# Final.net
KiCad netlist of a schematic drawn in EAGLE
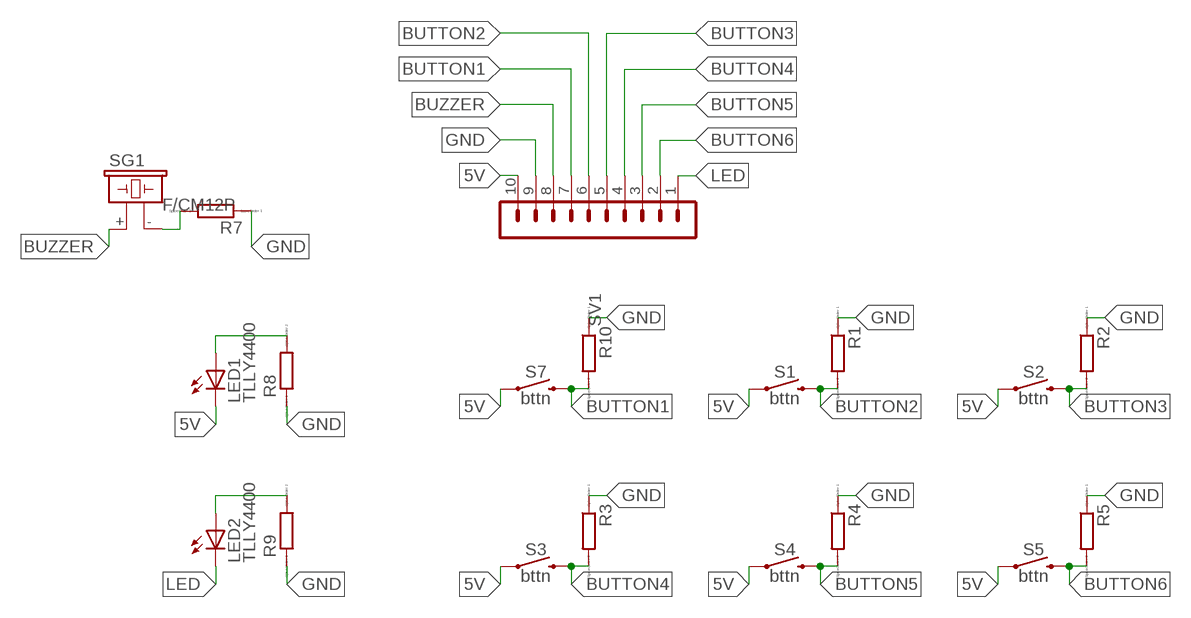
[diagram p0: schematic, sheet 1]

(export (version "E")
  (design (tool "Eeschema 10.0.6"))
  (components
    (comp (ref "LED1")
      (value "TLLY4400")
      (footprint "eagle-import:LED3MM")
      (fields (field (name "MF") "VISHAY SEMICONDUCTOR"))
      (libsource (lib "eagle-import") (part "TLLY4400"))
    )
    (comp (ref "LED2")
      (value "TLLY4400")
      (footprint "eagle-import:LED3MM")
      (fields (field (name "MF") "VISHAY SEMICONDUCTOR"))
      (libsource (lib "eagle-import") (part "TLLY4400"))
    )
    (comp (ref "R1")
      (value "R0204/7")
      (footprint "eagle-import:0204_7")
      (libsource (lib "eagle-import") (part "R0204/7"))
    )
    (comp (ref "R2")
      (value "R0204/7")
      (footprint "eagle-import:0204_7")
      (libsource (lib "eagle-import") (part "R0204/7"))
    )
    (comp (ref "R3")
      (value "R0204/7")
      (footprint "eagle-import:0204_7")
      (libsource (lib "eagle-import") (part "R0204/7"))
    )
    (comp (ref "R4")
      (value "R0204/7")
      (footprint "eagle-import:0204_7")
      (libsource (lib "eagle-import") (part "R0204/7"))
    )
    (comp (ref "R5")
      (value "R0204/7")
      (footprint "eagle-import:0204_7")
      (libsource (lib "eagle-import") (part "R0204/7"))
    )
    (comp (ref "R7")
      (value "R0204/7")
      (footprint "eagle-import:0204_7")
      (libsource (lib "eagle-import") (part "R0204/7"))
    )
    (comp (ref "R8")
      (value "R0204/7")
      (footprint "eagle-import:0204_7")
      (libsource (lib "eagle-import") (part "R0204/7"))
    )
    (comp (ref "R9")
      (value "R0204/7")
      (footprint "eagle-import:0204_7")
      (libsource (lib "eagle-import") (part "R0204/7"))
    )
    (comp (ref "R10")
      (value "R0204/7")
      (footprint "eagle-import:0204_7")
      (libsource (lib "eagle-import") (part "R0204/7"))
    )
    (comp (ref "S1")
      (value "bttn")
      (footprint "eagle-import:TACTILE_SWITCH_PTH_6.0MM")
      (libsource (lib "eagle-import") (part "MOMENTARY-SWITCH-SPST-PTH-6.0MM"))
    )
    (comp (ref "S2")
      (value "bttn")
      (footprint "eagle-import:TACTILE_SWITCH_PTH_6.0MM")
      (libsource (lib "eagle-import") (part "MOMENTARY-SWITCH-SPST-PTH-6.0MM"))
    )
    (comp (ref "S3")
      (value "bttn")
      (footprint "eagle-import:TACTILE_SWITCH_PTH_6.0MM")
      (libsource (lib "eagle-import") (part "MOMENTARY-SWITCH-SPST-PTH-6.0MM"))
    )
    (comp (ref "S4")
      (value "bttn")
      (footprint "eagle-import:TACTILE_SWITCH_PTH_6.0MM")
      (libsource (lib "eagle-import") (part "MOMENTARY-SWITCH-SPST-PTH-6.0MM"))
    )
    (comp (ref "S5")
      (value "bttn")
      (footprint "eagle-import:TACTILE_SWITCH_PTH_6.0MM")
      (libsource (lib "eagle-import") (part "MOMENTARY-SWITCH-SPST-PTH-6.0MM"))
    )
    (comp (ref "S7")
      (value "bttn")
      (footprint "eagle-import:TACTILE_SWITCH_PTH_6.0MM")
      (libsource (lib "eagle-import") (part "MOMENTARY-SWITCH-SPST-PTH-6.0MM"))
    )
    (comp (ref "SG1")
      (value "F/CM12P")
      (footprint "eagle-import:F_CM12P")
      (libsource (lib "eagle-import") (part "F/CM12P"))
    )
    (comp (ref "SV1")
      (value "MA10-1")
      (footprint "eagle-import:MA10-1")
      (libsource (lib "eagle-import") (part "MA10-1"))
    )
  )
  (nets
    (net (code "1") (name "5V") (class "Default")
      (node (ref "LED1") (pin "K") (pinfunction "C_K") (pintype "passive"))
      (node (ref "S1") (pin "1") (pinfunction "1_1") (pintype "passive"))
      (node (ref "S2") (pin "1") (pinfunction "1_1") (pintype "passive"))
      (node (ref "S3") (pin "1") (pinfunction "1_1") (pintype "passive"))
      (node (ref "S4") (pin "1") (pinfunction "1_1") (pintype "passive"))
      (node (ref "S5") (pin "1") (pinfunction "1_1") (pintype "passive"))
      (node (ref "S7") (pin "1") (pinfunction "1_1") (pintype "passive"))
      (node (ref "SV1") (pin "10") (pinfunction "10_10") (pintype "passive"))
    )
    (net (code "2") (name "BUTTON1") (class "Default")
      (node (ref "R10") (pin "2") (pinfunction "2_2") (pintype "passive"))
      (node (ref "S7") (pin "3") (pinfunction "2_3") (pintype "passive"))
      (node (ref "SV1") (pin "7") (pinfunction "7_7") (pintype "passive"))
    )
    (net (code "3") (name "BUTTON2") (class "Default")
      (node (ref "R1") (pin "2") (pinfunction "2_2") (pintype "passive"))
      (node (ref "S1") (pin "3") (pinfunction "2_3") (pintype "passive"))
      (node (ref "SV1") (pin "6") (pinfunction "6_6") (pintype "passive"))
    )
    (net (code "4") (name "BUTTON3") (class "Default")
      (node (ref "R2") (pin "2") (pinfunction "2_2") (pintype "passive"))
      (node (ref "S2") (pin "3") (pinfunction "2_3") (pintype "passive"))
      (node (ref "SV1") (pin "5") (pinfunction "5_5") (pintype "passive"))
    )
    (net (code "5") (name "BUTTON4") (class "Default")
      (node (ref "R3") (pin "2") (pinfunction "2_2") (pintype "passive"))
      (node (ref "S3") (pin "3") (pinfunction "2_3") (pintype "passive"))
      (node (ref "SV1") (pin "4") (pinfunction "4_4") (pintype "passive"))
    )
    (net (code "6") (name "BUTTON5") (class "Default")
      (node (ref "R4") (pin "2") (pinfunction "2_2") (pintype "passive"))
      (node (ref "S4") (pin "3") (pinfunction "2_3") (pintype "passive"))
      (node (ref "SV1") (pin "3") (pinfunction "3_3") (pintype "passive"))
    )
    (net (code "7") (name "BUTTON6") (class "Default")
      (node (ref "R5") (pin "2") (pinfunction "2_2") (pintype "passive"))
      (node (ref "S5") (pin "3") (pinfunction "2_3") (pintype "passive"))
      (node (ref "SV1") (pin "2") (pinfunction "2_2") (pintype "passive"))
    )
    (net (code "8") (name "BUZZER") (class "Default")
      (node (ref "SG1") (pin "+") (pinfunction "1_+") (pintype "passive"))
      (node (ref "SV1") (pin "8") (pinfunction "8_8") (pintype "passive"))
    )
    (net (code "9") (name "GND") (class "Default")
      (node (ref "R1") (pin "1") (pinfunction "1_1") (pintype "passive"))
      (node (ref "R10") (pin "1") (pinfunction "1_1") (pintype "passive"))
      (node (ref "R2") (pin "1") (pinfunction "1_1") (pintype "passive"))
      (node (ref "R3") (pin "1") (pinfunction "1_1") (pintype "passive"))
      (node (ref "R4") (pin "1") (pinfunction "1_1") (pintype "passive"))
      (node (ref "R5") (pin "1") (pinfunction "1_1") (pintype "passive"))
      (node (ref "R7") (pin "1") (pinfunction "1_1") (pintype "passive"))
      (node (ref "R8") (pin "1") (pinfunction "1_1") (pintype "passive"))
      (node (ref "R9") (pin "1") (pinfunction "1_1") (pintype "passive"))
      (node (ref "SV1") (pin "9") (pinfunction "9_9") (pintype "passive"))
    )
    (net (code "10") (name "LED") (class "Default")
      (node (ref "LED2") (pin "K") (pinfunction "C_K") (pintype "passive"))
      (node (ref "SV1") (pin "1") (pinfunction "1_1") (pintype "passive"))
    )
    (net (code "11") (name "Net-(LED1-PadA)") (class "Default")
      (node (ref "LED1") (pin "A") (pinfunction "A_A") (pintype "passive"))
      (node (ref "R8") (pin "2") (pinfunction "2_2") (pintype "passive"))
    )
    (net (code "12") (name "Net-(LED2-PadA)") (class "Default")
      (node (ref "LED2") (pin "A") (pinfunction "A_A") (pintype "passive"))
      (node (ref "R9") (pin "2") (pinfunction "2_2") (pintype "passive"))
    )
    (net (code "13") (name "Net-(SG1-2)") (class "Default")
      (node (ref "R7") (pin "2") (pinfunction "2_2") (pintype "passive"))
      (node (ref "SG1") (pin "-") (pinfunction "2_-") (pintype "passive"))
    )
  )
)
